# CAN0.net
KiCad netlist of a schematic drawn in Altium Designer
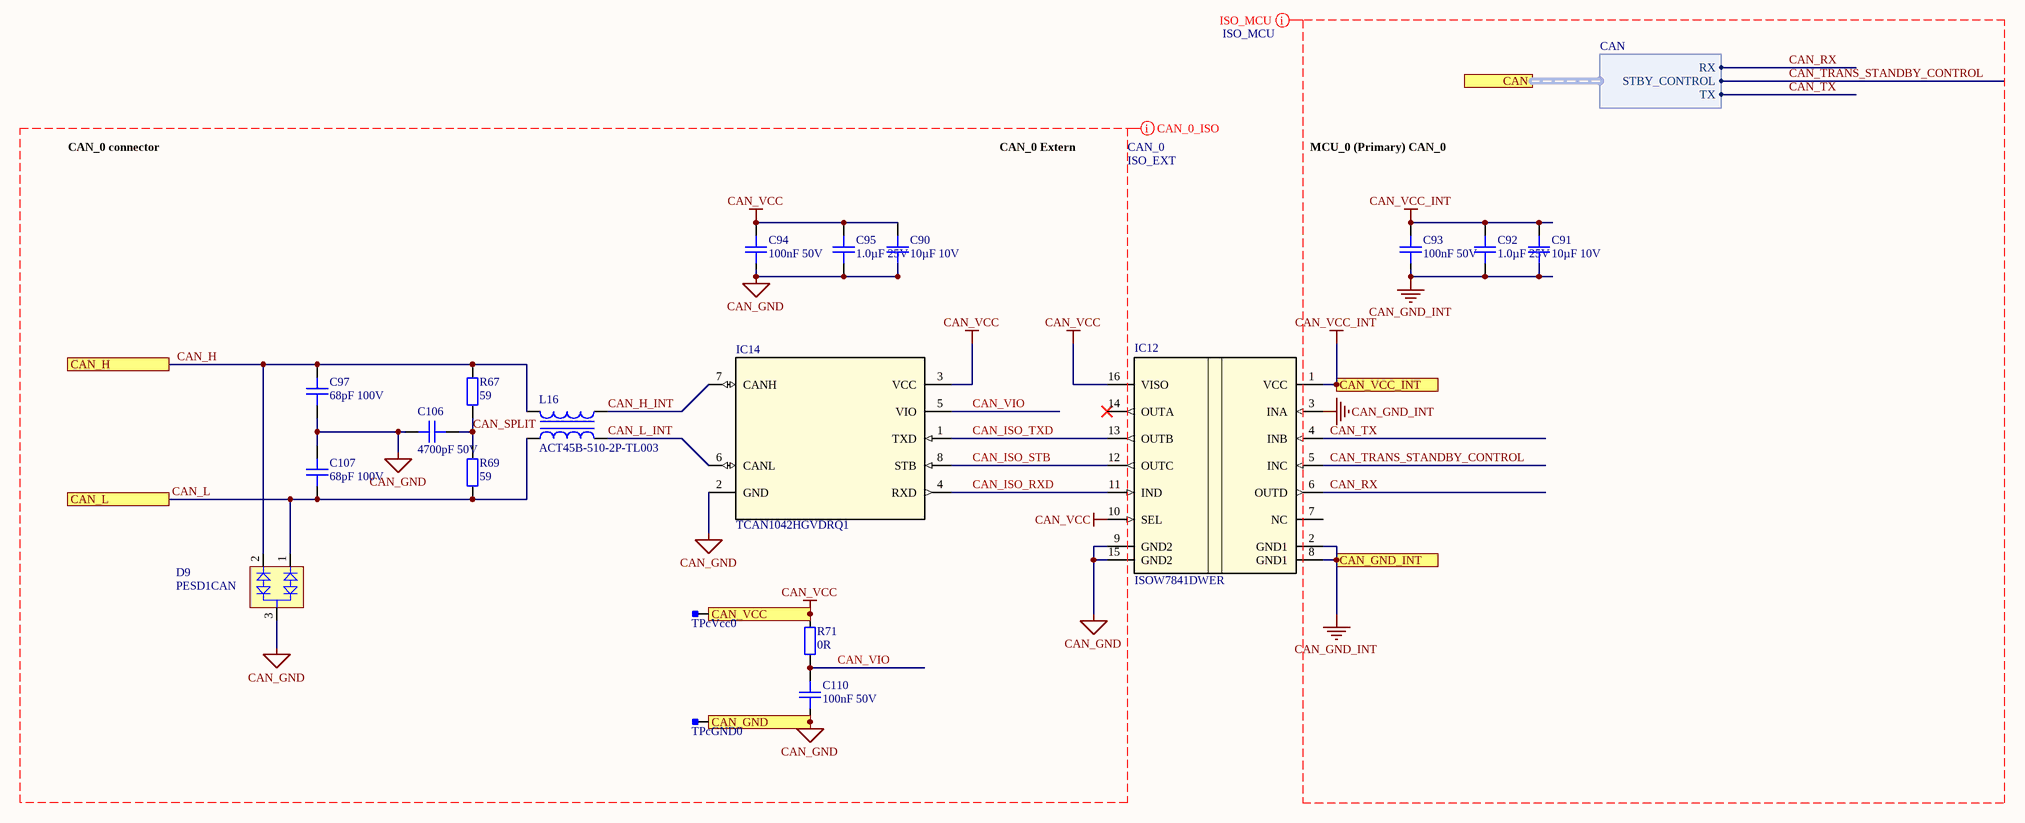
[diagram p0: CAN0.SchDoc]

(export (version "E")
  (design (tool "Eeschema 10.0.6"))
  (components
    (comp (ref "C90")
      (value "10µF 10V")
      (footprint "0805C")
      (description "Ceramic, 10µF, ±10%, 10V, X7R, –55 to 125°C, 0805 (2012),RoHS, Automotive")
      (fields (field (name "PART NUMBER") "GCJ21BR71A106KE01") (field (name "TOLERANCE") "±10%"))
      (libsource (lib "master-010106") (part "gen_C_ceramic_10u_10V_X7R_0805"))
    )
    (comp (ref "C91")
      (value "10µF 10V")
      (footprint "0805C")
      (description "Ceramic, 10µF, ±10%, 10V, X7R, –55 to 125°C, 0805 (2012),RoHS, Automotive")
      (fields (field (name "PART NUMBER") "GCJ21BR71A106KE01") (field (name "TOLERANCE") "±10%"))
      (libsource (lib "master-010106") (part "gen_C_ceramic_10u_10V_X7R_0805"))
    )
    (comp (ref "C92")
      (value "1.0µF 25V")
      (footprint "0603C")
      (description "Ceramic, 1.0µF, ±10%, 25V, X7R, –55 to 125°C, 0603 (1608),RoHS, Automotive")
      (fields (field (name "PART NUMBER") "GCJ188R71E105KA01") (field (name "TOLERANCE") "±10%"))
      (libsource (lib "master-010106") (part "gen_C_ceramic_1u_25V_X7R_0603"))
    )
    (comp (ref "C93")
      (value "100nF 50V")
      (footprint "0603C")
      (description "Ceramic, 100nF, ±10%, 50V, X7R, –55 to 125°C, 0603 (1608),RoHS, Automotive")
      (fields (field (name "PART NUMBER") "GCJ188R71H104KA12") (field (name "TOLERANCE") "±10%"))
      (libsource (lib "master-010106") (part "C"))
    )
    (comp (ref "C94")
      (value "100nF 50V")
      (footprint "0603C")
      (description "Ceramic, 100nF, ±10%, 50V, X7R, –55 to 125°C, 0603 (1608),RoHS, Automotive")
      (fields (field (name "PART NUMBER") "GCJ188R71H104KA12") (field (name "TOLERANCE") "±10%"))
      (libsource (lib "master-010106") (part "C"))
    )
    (comp (ref "C95")
      (value "1.0µF 25V")
      (footprint "0603C")
      (description "Ceramic, 1.0µF, ±10%, 25V, X7R, –55 to 125°C, 0603 (1608),RoHS, Automotive")
      (fields (field (name "PART NUMBER") "GCJ188R71E105KA01") (field (name "TOLERANCE") "±10%"))
      (libsource (lib "master-010106") (part "gen_C_ceramic_1u_25V_X7R_0603"))
    )
    (comp (ref "C97")
      (value "68pF 100V")
      (footprint "0603C")
      (description "Ceramic, 68pF, ±5%, 100V, X7R, 25 to 125°C, 0603 (1608),RoHS, Automotive")
      (fields (field (name "PART NUMBER") "GCM1885C2A680JA16") (field (name "TOLERANCE") "±5%"))
      (libsource (lib "master-010106") (part "gen_C_ceramic_68p_100V_X7R_0603"))
    )
    (comp (ref "C106")
      (value "4700pF 50V")
      (footprint "0603C")
      (description "Ceramic, 4700pF, 0603, ±5%, 50V, C0G")
      (fields (field (name "PART NUMBER") "GRT1885C1H472JA02"))
      (libsource (lib "master-010106") (part "C"))
    )
    (comp (ref "C107")
      (value "68pF 100V")
      (footprint "0603C")
      (description "Ceramic, 68pF, ±5%, 100V, X7R, 25 to 125°C, 0603 (1608),RoHS, Automotive")
      (fields (field (name "PART NUMBER") "GCM1885C2A680JA16") (field (name "TOLERANCE") "±5%"))
      (libsource (lib "master-010106") (part "gen_C_ceramic_68p_100V_X7R_0603"))
    )
    (comp (ref "C110")
      (value "100nF 50V")
      (footprint "0603C")
      (description "Ceramic, 100nF, ±10%, 50V, X7R, –55 to 125°C, 0603 (1608),RoHS, Automotive")
      (fields (field (name "PART NUMBER") "GCJ188R71H104KA12") (field (name "TOLERANCE") "±10%"))
      (libsource (lib "master-010106") (part "C"))
    )
    (comp (ref "D9")
      (value "PESD1CAN")
      (footprint "NXP-SOT23-3_V")
      (description "CAN Bus ESD Protection Diode, 200 W, 24 V, -65 to 150 degC, 3-Pin SOT23, RoHS, Tape and Reel")
      (fields (field (name "MANUFACTURER") "NXP Semiconductors"))
      (libsource (lib "Altium Content Vault") (part "NXP-PESD1CAN-SOT23-3"))
    )
    (comp (ref "IC12")
      (value "ISOW7841DWER")
      (footprint "DWE0016A")
      (description "Imported")
      (fields (field (name "MANUFACTURER") "Texas Instruments"))
      (libsource (lib "ti-import") (part "ISOW7841DWER"))
    )
    (comp (ref "IC14")
      (value "TCAN1042HGVDRQ1")
      (footprint "D0008A_N")
      (description "Imported")
      (fields (field (name "PARTNUMBER") "TCAN1042HGVDQ1") (field (name "MANUFACTURER") "Texas Instruments"))
      (libsource (lib "ti-import") (part "TCAN1042HGVDRQ1"))
    )
    (comp (ref "L16")
      (value "ACT45B-510-2P-TL003")
      (footprint "TDK-ACT45B-510-2P-TL003-4_V")
      (fields (field (name "MANUFACTURER") "TDK"))
      (libsource (lib "Altium Content Vault") (part "TDK-ACXXXXX-XXX-2P-T000-4"))
    )
    (comp (ref "R67")
      (value "59")
      (footprint "0805R")
      (description "SMD Resistor 59R 0805")
      (fields (field (name "PART NUMBER") "gen_R_62R_0603") (field (name "TOLERANCE") "1%"))
      (libsource (lib "master-010106") (part "gen_R_59R_0805"))
    )
    (comp (ref "R69")
      (value "59")
      (footprint "0805R")
      (description "SMD Resistor 59R 0805")
      (fields (field (name "PART NUMBER") "gen_R_62R_0603") (field (name "TOLERANCE") "1%"))
      (libsource (lib "master-010106") (part "gen_R_59R_0805"))
    )
    (comp (ref "R71")
      (value "0R")
      (footprint "0603R")
      (description "SMD Resistor 0R 0603")
      (fields (field (name "PART NUMBER") "gen_R_0R_0603") (field (name "POWER") "0.1W"))
      (libsource (lib "master-010106") (part "gen_R_0R_0603"))
    )
    (comp (ref "TPcGND0")
      (value "Testpoint_Square")
      (footprint "Testpoint_S1")
      (description "Testpoint, square")
      (libsource (lib "OE750") (part "Testpoint_Square"))
    )
    (comp (ref "TPcVcc0")
      (value "Testpoint_Square")
      (footprint "Testpoint_S1")
      (description "Testpoint, square")
      (libsource (lib "OE750") (part "Testpoint_Square"))
    )
  )
  (nets
    (net (code "2") (name "/CAN_H") (class "Default")
      (node (ref "C97") (pin "2") (pinfunction "2_2") (pintype "passive"))
      (node (ref "D9") (pin "2") (pinfunction "K2_2") (pintype "passive"))
      (node (ref "L16") (pin "2") (pinfunction "2_2") (pintype "passive"))
      (node (ref "R67") (pin "2") (pinfunction "2_2") (pintype "passive"))
    )
    (net (code "3") (name "/CAN_H_INT") (class "Default")
      (node (ref "IC14") (pin "7") (pinfunction "CANH_7") (pintype "bidirectional"))
      (node (ref "L16") (pin "3") (pinfunction "3_3") (pintype "passive"))
    )
    (net (code "4") (name "/CAN_ISO_RXD") (class "Default")
      (node (ref "IC12") (pin "11") (pinfunction "IND_11") (pintype "input"))
      (node (ref "IC14") (pin "4") (pinfunction "RXD_4") (pintype "output"))
    )
    (net (code "5") (name "/CAN_ISO_STB") (class "Default")
      (node (ref "IC12") (pin "12") (pinfunction "OUTC_12") (pintype "output"))
      (node (ref "IC14") (pin "8") (pinfunction "STB_8") (pintype "input"))
    )
    (net (code "6") (name "/CAN_ISO_TXD") (class "Default")
      (node (ref "IC12") (pin "13") (pinfunction "OUTB_13") (pintype "output"))
      (node (ref "IC14") (pin "1") (pinfunction "TXD_1") (pintype "input"))
    )
    (net (code "7") (name "/CAN_L") (class "Default")
      (node (ref "C107") (pin "1") (pinfunction "1_1") (pintype "passive"))
      (node (ref "D9") (pin "1") (pinfunction "K1_1") (pintype "passive"))
      (node (ref "L16") (pin "1") (pinfunction "1_1") (pintype "passive"))
      (node (ref "R69") (pin "1") (pinfunction "1_1") (pintype "passive"))
    )
    (net (code "8") (name "/CAN_L_INT") (class "Default")
      (node (ref "IC14") (pin "6") (pinfunction "CANL_6") (pintype "bidirectional"))
      (node (ref "L16") (pin "4") (pinfunction "4_4") (pintype "passive"))
    )
    (net (code "9") (name "/CAN_RX") (class "Default")
      (node (ref "IC12") (pin "6") (pinfunction "OUTD_6") (pintype "output"))
    )
    (net (code "10") (name "/CAN_SPLIT") (class "Default")
      (node (ref "C106") (pin "2") (pinfunction "2_2") (pintype "passive"))
      (node (ref "R67") (pin "1") (pinfunction "1_1") (pintype "passive"))
      (node (ref "R69") (pin "2") (pinfunction "2_2") (pintype "passive"))
    )
    (net (code "11") (name "/CAN_TRANS_STANDBY_CONTROL") (class "Default")
      (node (ref "IC12") (pin "5") (pinfunction "INC_5") (pintype "input"))
    )
    (net (code "12") (name "/CAN_TX") (class "Default")
      (node (ref "IC12") (pin "4") (pinfunction "INB_4") (pintype "input"))
    )
    (net (code "13") (name "/CAN_VIO") (class "Default")
      (node (ref "C110") (pin "2") (pinfunction "2_2") (pintype "passive"))
      (node (ref "IC14") (pin "5") (pinfunction "VIO_5") (pintype "power_in"))
      (node (ref "R71") (pin "2") (pinfunction "2_2") (pintype "passive"))
    )
    (net (code "15") (name "CAN_GND") (class "Default")
      (node (ref "C106") (pin "1") (pinfunction "1_1") (pintype "passive"))
      (node (ref "C107") (pin "2") (pinfunction "2_2") (pintype "passive"))
      (node (ref "C110") (pin "1") (pinfunction "1_1") (pintype "passive"))
      (node (ref "C90") (pin "2") (pinfunction "2_2") (pintype "passive"))
      (node (ref "C94") (pin "1") (pinfunction "1_1") (pintype "passive"))
      (node (ref "C95") (pin "1") (pinfunction "1_1") (pintype "passive"))
      (node (ref "C97") (pin "1") (pinfunction "1_1") (pintype "passive"))
      (node (ref "D9") (pin "3") (pinfunction "C_3") (pintype "passive"))
      (node (ref "IC12") (pin "15") (pinfunction "GND2_15") (pintype "power_in"))
      (node (ref "IC12") (pin "9") (pinfunction "GND2_9") (pintype "power_in"))
      (node (ref "IC14") (pin "2") (pinfunction "GND_2") (pintype "power_in"))
      (node (ref "TPcGND0") (pin "1") (pinfunction "1_1") (pintype "passive"))
    )
    (net (code "16") (name "CAN_GND_INT") (class "Default")
      (node (ref "C91") (pin "2") (pinfunction "2_2") (pintype "passive"))
      (node (ref "C92") (pin "1") (pinfunction "1_1") (pintype "passive"))
      (node (ref "C93") (pin "1") (pinfunction "1_1") (pintype "passive"))
      (node (ref "IC12") (pin "2") (pinfunction "GND1_2") (pintype "power_in"))
      (node (ref "IC12") (pin "3") (pinfunction "INA_3") (pintype "input"))
      (node (ref "IC12") (pin "8") (pinfunction "GND1_8") (pintype "power_in"))
    )
    (net (code "17") (name "CAN_VCC") (class "Default")
      (node (ref "C90") (pin "1") (pinfunction "1_1") (pintype "passive"))
      (node (ref "C94") (pin "2") (pinfunction "2_2") (pintype "passive"))
      (node (ref "C95") (pin "2") (pinfunction "2_2") (pintype "passive"))
      (node (ref "IC12") (pin "10") (pinfunction "SEL_10") (pintype "input"))
      (node (ref "IC12") (pin "16") (pinfunction "VISO_16") (pintype "power_in"))
      (node (ref "IC14") (pin "3") (pinfunction "VCC_3") (pintype "power_in"))
      (node (ref "R71") (pin "1") (pinfunction "1_1") (pintype "passive"))
      (node (ref "TPcVcc0") (pin "1") (pinfunction "1_1") (pintype "passive"))
    )
    (net (code "18") (name "CAN_VCC_INT") (class "Default")
      (node (ref "C91") (pin "1") (pinfunction "1_1") (pintype "passive"))
      (node (ref "C92") (pin "2") (pinfunction "2_2") (pintype "passive"))
      (node (ref "C93") (pin "2") (pinfunction "2_2") (pintype "passive"))
      (node (ref "IC12") (pin "1") (pinfunction "VCC_1") (pintype "power_in"))
    )
    (net (code "19") (name "unconnected-(IC12-NC-Pad7)") (class "Default")
      (node (ref "IC12") (pin "7") (pinfunction "NC_7") (pintype "passive"))
    )
    (net (code "20") (name "unconnected-(IC12-OUTA-Pad14)") (class "Default")
      (node (ref "IC12") (pin "14") (pinfunction "OUTA_14") (pintype "output+no_connect"))
    )
  )
)
